# Interface_gratis.net
KiCad netlist of a schematic drawn in Altium Designer
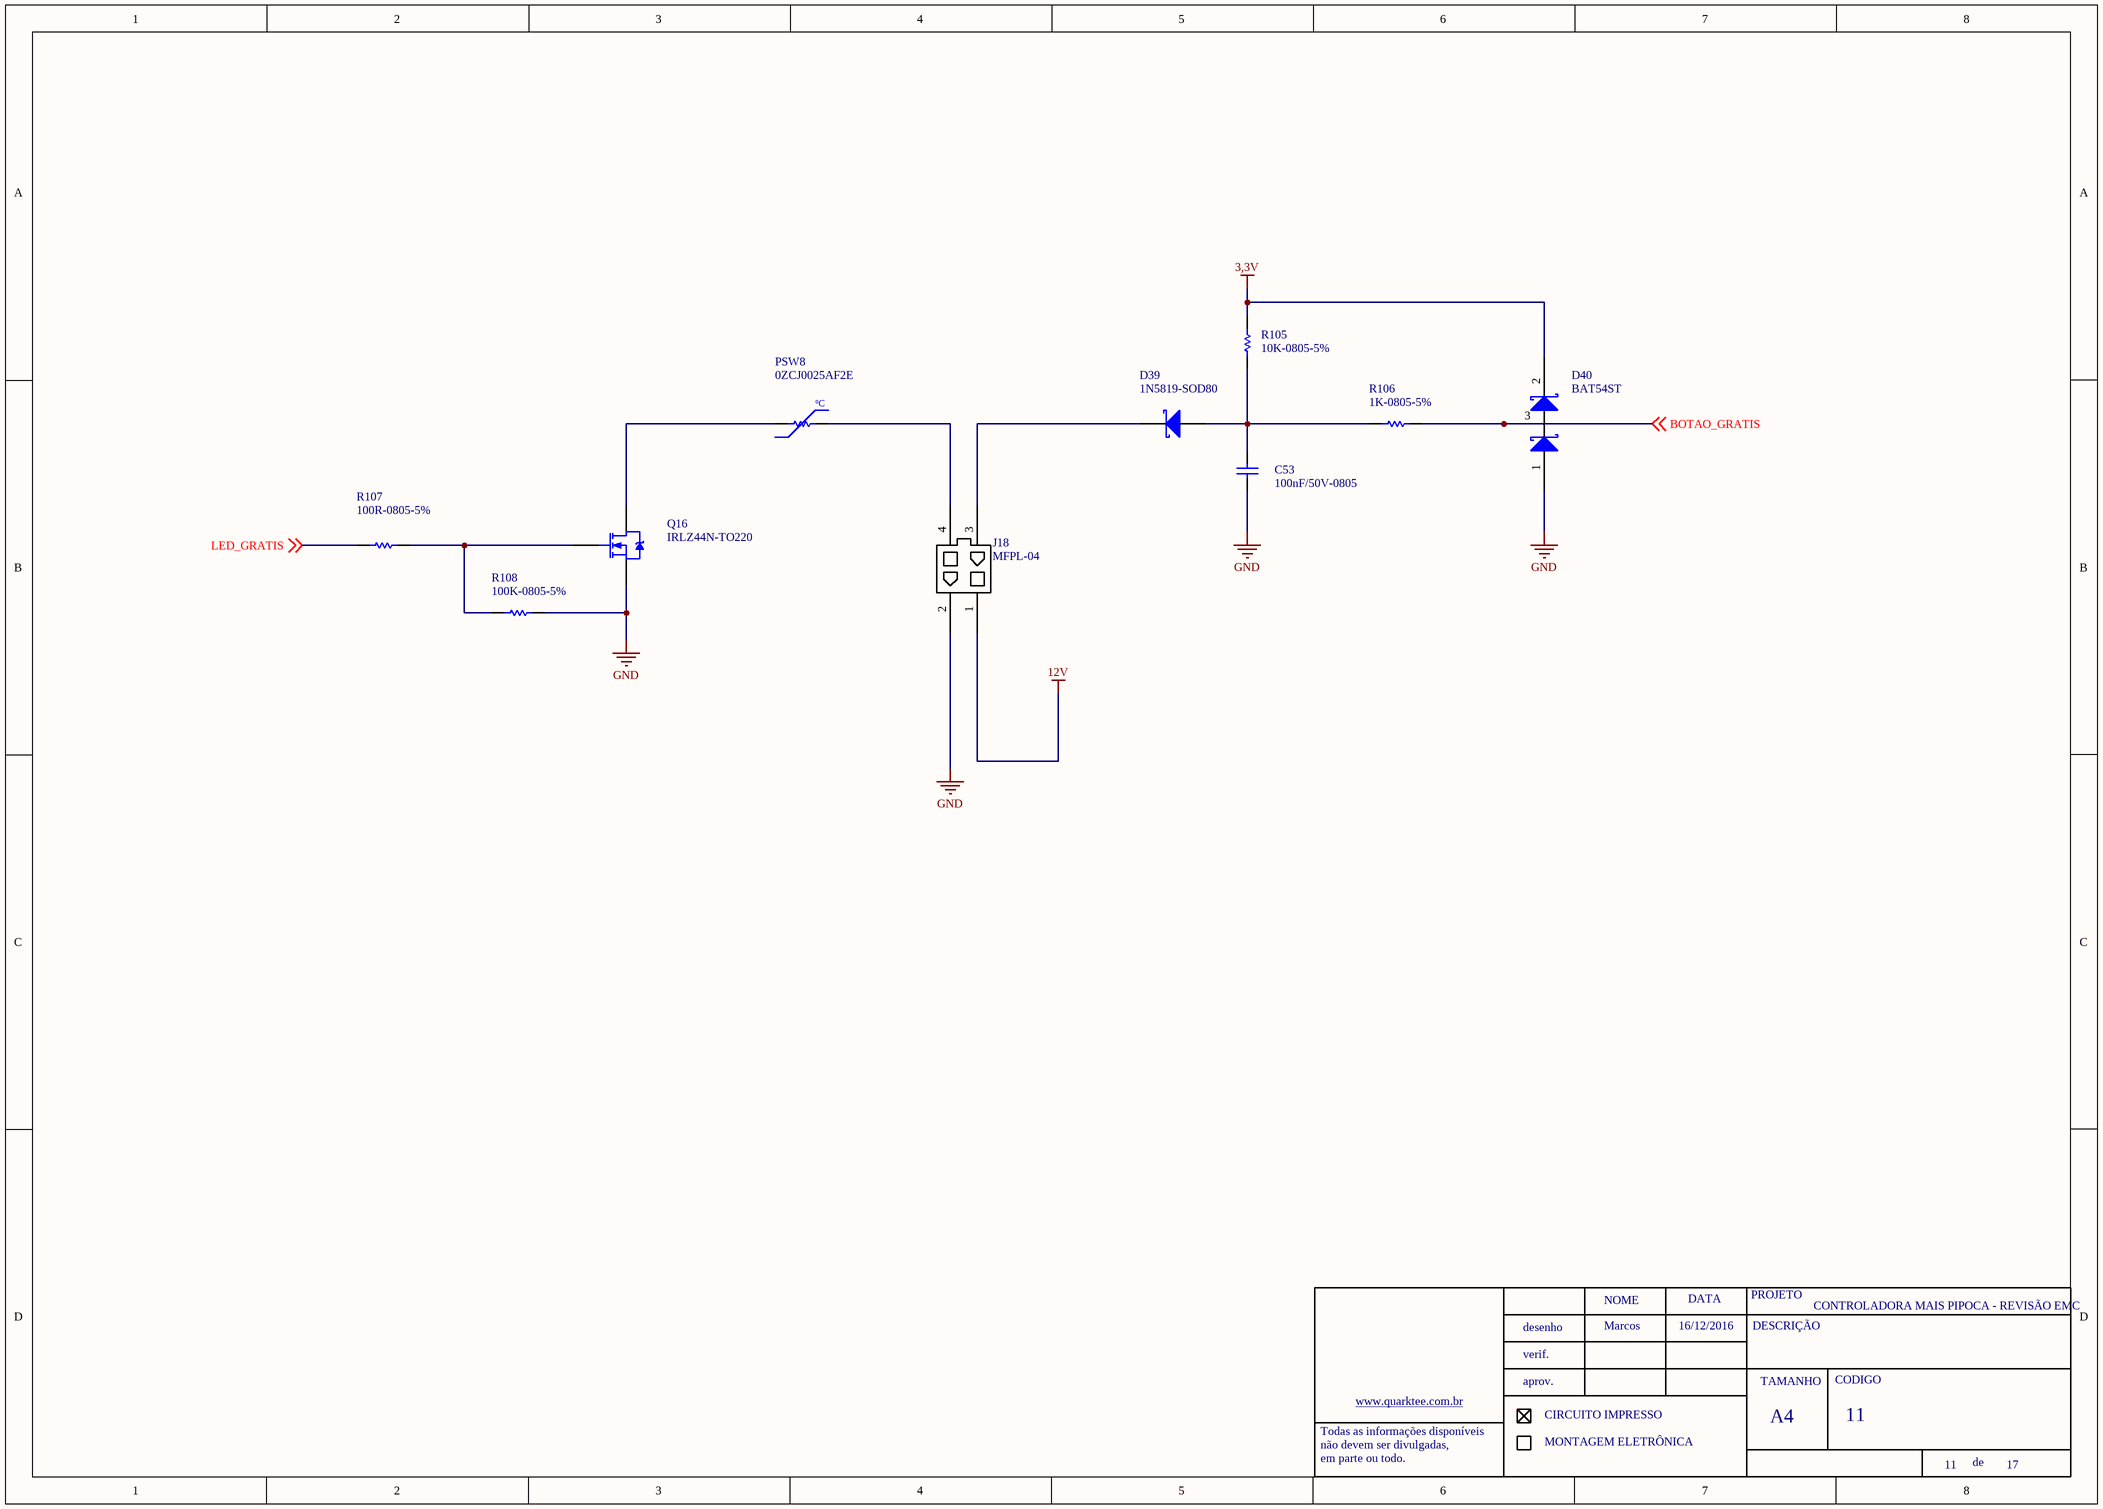
[diagram p0: Interface_gratis.SchDoc]

(export (version "E")
  (design (tool "Eeschema 10.0.6"))
  (components
    (comp (ref "C53")
      (value "100nF/50V-0805")
      (footprint "0805-REVISADO ONDA")
      (libsource (lib "AquinoLib") (part "100nF/50-0805-NPO"))
    )
    (comp (ref "D39")
      (value "1N5819-SOD80")
      (footprint "MINIMLEF/SOD80 - REVISADO ONDA")
      (libsource (lib "AquinoLib") (part "1N5819-SOD80"))
    )
    (comp (ref "D40")
      (value "BAT54ST")
      (footprint "SOT23 - REVISADO ONDA")
      (libsource (lib "AquinoLib") (part "BAT54ST"))
    )
    (comp (ref "J18") (value "MFPL-04") (libsource (lib "AquinoLib") (part "MFPL-04")))
    (comp (ref "PSW8")
      (value "0ZCJ0025AF2E")
      (footprint "1206-REVISADO ONDA")
      (description "PTC 2A-120V")
      (libsource (lib "AquinoLib") (part "PTC 2A-120V"))
    )
    (comp (ref "Q16")
      (value "IRLZ44N-TO220")
      (footprint "TO220-3 EM PÉ")
      (libsource (lib "ChaveDigital3") (part "IRLZ44N-TO220"))
    )
    (comp (ref "R105")
      (value "10K-0805-5%")
      (footprint "0805-REVISADO ONDA")
      (libsource (lib "AquinoLib") (part "10K-0805-5%"))
    )
    (comp (ref "R106")
      (value "1K-0805-5%")
      (footprint "0805-REVISADO ONDA")
      (libsource (lib "AquinoLib") (part "1K-0805-5%"))
    )
    (comp (ref "R107")
      (value "100R-0805-5%")
      (footprint "0805-REVISADO ONDA")
      (libsource (lib "AquinoLib") (part "100R-0805-5%"))
    )
    (comp (ref "R108")
      (value "100K-0805-5%")
      (footprint "0805-REVISADO ONDA")
      (libsource (lib "AquinoLib") (part "100K-0805-5%"))
    )
  )
  (nets
    (net (code "1") (name "3,3V") (class "Default")
      (node (ref "D40") (pin "2") (pinfunction "2_2") (pintype "passive"))
      (node (ref "R105") (pin "2") (pinfunction "2_2") (pintype "passive"))
    )
    (net (code "2") (name "12V") (class "Default")
      (node (ref "J18") (pin "1") (pinfunction "1_1") (pintype "passive"))
    )
    (net (code "3") (name "BOTAO_GRATIS") (class "Default")
      (node (ref "D40") (pin "3") (pinfunction "3_3") (pintype "passive"))
      (node (ref "R106") (pin "2") (pinfunction "2_2") (pintype "passive"))
    )
    (net (code "4") (name "GND") (class "Default")
      (node (ref "C53") (pin "1") (pinfunction "1_1") (pintype "passive"))
      (node (ref "D40") (pin "1") (pinfunction "1_1") (pintype "passive"))
      (node (ref "J18") (pin "2") (pinfunction "2_2") (pintype "passive"))
      (node (ref "Q16") (pin "3") (pinfunction "S_3") (pintype "passive"))
      (node (ref "R108") (pin "2") (pinfunction "2_2") (pintype "passive"))
    )
    (net (code "5") (name "LED_GRATIS") (class "Default")
      (node (ref "R107") (pin "1") (pinfunction "1_1") (pintype "passive"))
    )
    (net (code "6") (name "Net-(D39-A)") (class "Default")
      (node (ref "C53") (pin "2") (pinfunction "2_2") (pintype "passive"))
      (node (ref "D39") (pin "1") (pinfunction "A_1") (pintype "passive"))
      (node (ref "R105") (pin "1") (pinfunction "1_1") (pintype "passive"))
      (node (ref "R106") (pin "1") (pinfunction "1_1") (pintype "passive"))
    )
    (net (code "7") (name "Net-(D39-K)") (class "Default")
      (node (ref "D39") (pin "2") (pinfunction "K_2") (pintype "passive"))
      (node (ref "J18") (pin "3") (pinfunction "3_3") (pintype "passive"))
    )
    (net (code "8") (name "Net-(J18-Pad4)") (class "Default")
      (node (ref "J18") (pin "4") (pinfunction "4_4") (pintype "passive"))
      (node (ref "PSW8") (pin "2") (pinfunction "2_2") (pintype "passive"))
    )
    (net (code "9") (name "Net-(Q16-D)") (class "Default")
      (node (ref "PSW8") (pin "1") (pinfunction "1_1") (pintype "passive"))
      (node (ref "Q16") (pin "2") (pinfunction "D_2") (pintype "passive"))
    )
    (net (code "10") (name "Net-(Q16-G)") (class "Default")
      (node (ref "Q16") (pin "1") (pinfunction "G_1") (pintype "passive"))
      (node (ref "R107") (pin "2") (pinfunction "2_2") (pintype "passive"))
      (node (ref "R108") (pin "1") (pinfunction "1_1") (pintype "passive"))
    )
  )
)
